# expansion_module_test_pads.net
KiCad netlist of a schematic drawn in EAGLE
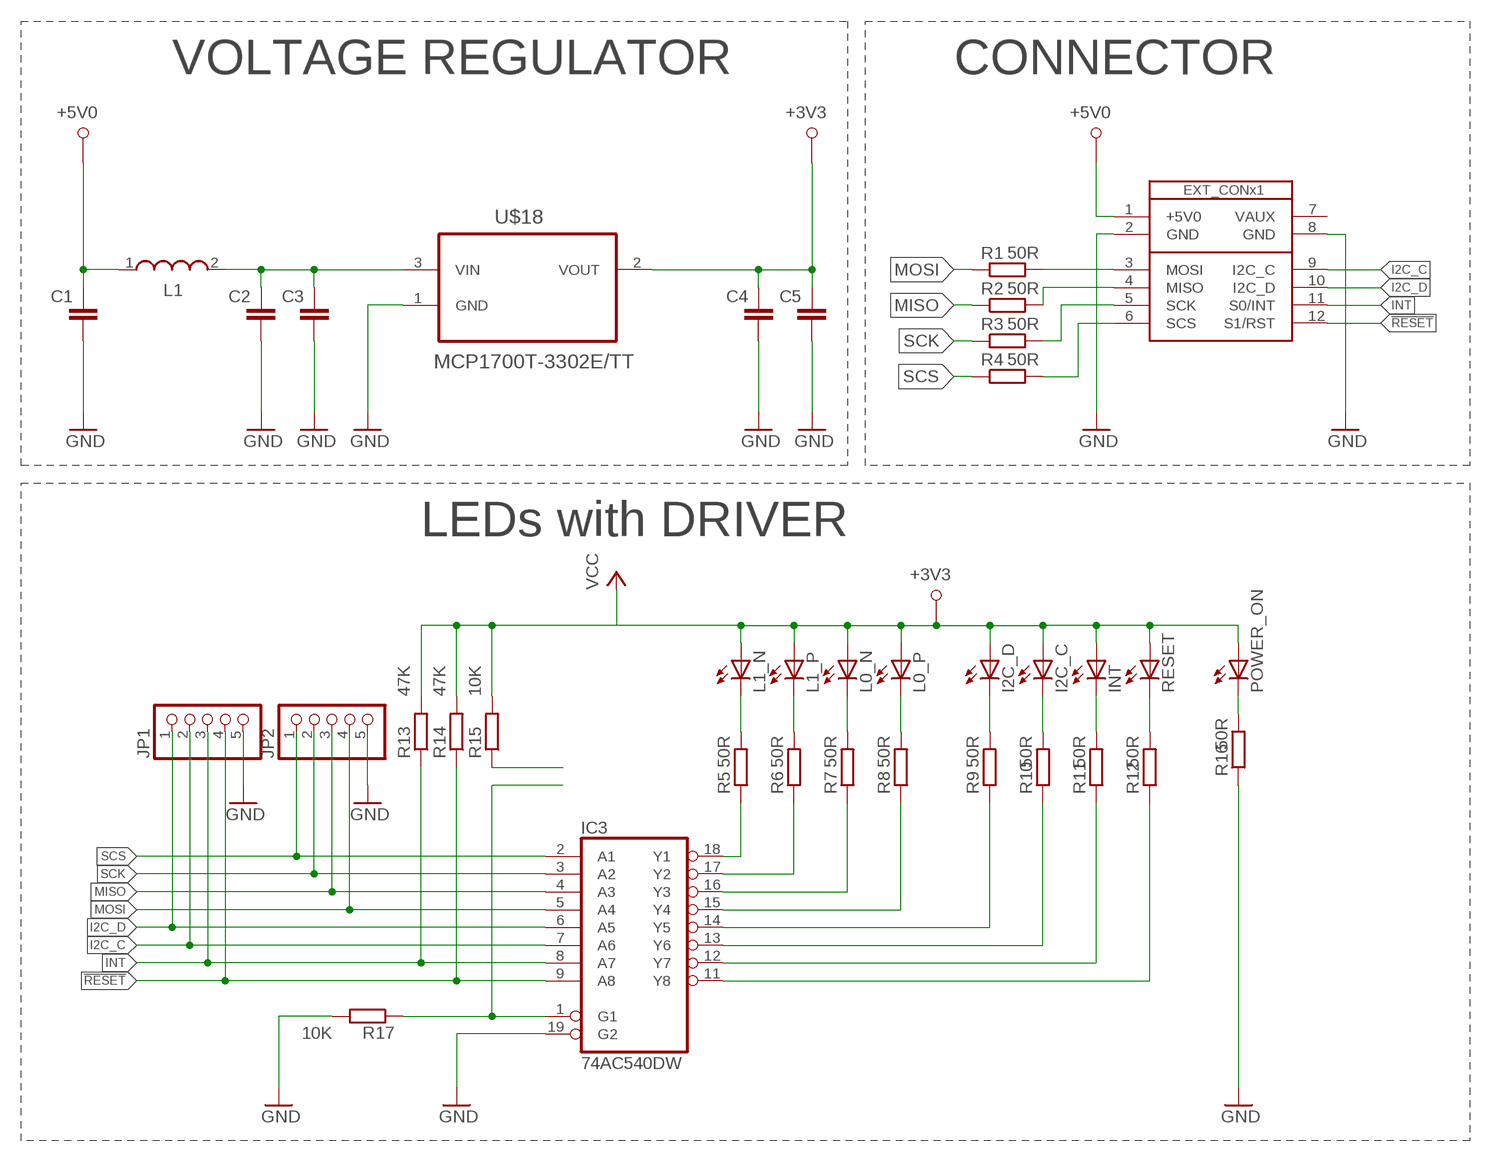
[diagram p0: schematic, sheet 1]

(export (version "E")
  (design (tool "Eeschema 10.0.6"))
  (components
    (comp (ref "C1")
      (value "C-EUC0805")
      (footprint "eagle-import:C0805")
      (libsource (lib "eagle-import") (part "C-EUC0805"))
    )
    (comp (ref "C2")
      (value "C-EUC0805")
      (footprint "eagle-import:C0805")
      (libsource (lib "eagle-import") (part "C-EUC0805"))
    )
    (comp (ref "C3")
      (value "C-EUC0805")
      (footprint "eagle-import:C0805")
      (libsource (lib "eagle-import") (part "C-EUC0805"))
    )
    (comp (ref "C4")
      (value "C-EUC0805")
      (footprint "eagle-import:C0805")
      (libsource (lib "eagle-import") (part "C-EUC0805"))
    )
    (comp (ref "C5")
      (value "C-EUC0805")
      (footprint "eagle-import:C0805")
      (libsource (lib "eagle-import") (part "C-EUC0805"))
    )
    (comp (ref "I2C_C")
      (value "LEDCHIPLED_0805")
      (footprint "eagle-import:CHIPLED_0805")
      (libsource (lib "eagle-import") (part "LEDCHIPLED_0805"))
    )
    (comp (ref "I2C_D")
      (value "LEDCHIPLED_0805")
      (footprint "eagle-import:CHIPLED_0805")
      (libsource (lib "eagle-import") (part "LEDCHIPLED_0805"))
    )
    (comp (ref "IC3")
      (value "74AC540DW")
      (footprint "eagle-import:SO20W")
      (libsource (lib "eagle-import") (part "74540DWAC"))
    )
    (comp (ref "INT")
      (value "LEDCHIPLED_0805")
      (footprint "eagle-import:CHIPLED_0805")
      (libsource (lib "eagle-import") (part "LEDCHIPLED_0805"))
    )
    (comp (ref "JP1")
      (value "PINHD-1X5")
      (footprint "eagle-import:1X05")
      (libsource (lib "eagle-import") (part "PINHD-1X5"))
    )
    (comp (ref "JP2")
      (value "PINHD-1X5")
      (footprint "eagle-import:1X05")
      (libsource (lib "eagle-import") (part "PINHD-1X5"))
    )
    (comp (ref "L0_N")
      (value "LEDCHIPLED_0805")
      (footprint "eagle-import:CHIPLED_0805")
      (libsource (lib "eagle-import") (part "LEDCHIPLED_0805"))
    )
    (comp (ref "L0_P")
      (value "LEDCHIPLED_0805")
      (footprint "eagle-import:CHIPLED_0805")
      (libsource (lib "eagle-import") (part "LEDCHIPLED_0805"))
    )
    (comp (ref "L1")
      (value "WE-LQ_1210")
      (footprint "eagle-import:WE-LQ_M")
      (libsource (lib "eagle-import") (part "WE-LQ_1210"))
    )
    (comp (ref "L1_N")
      (value "LEDCHIPLED_0805")
      (footprint "eagle-import:CHIPLED_0805")
      (libsource (lib "eagle-import") (part "LEDCHIPLED_0805"))
    )
    (comp (ref "L1_P")
      (value "LEDCHIPLED_0805")
      (footprint "eagle-import:CHIPLED_0805")
      (libsource (lib "eagle-import") (part "LEDCHIPLED_0805"))
    )
    (comp (ref "POWER_ON")
      (value "LEDCHIPLED_0805")
      (footprint "eagle-import:CHIPLED_0805")
      (libsource (lib "eagle-import") (part "LEDCHIPLED_0805"))
    )
    (comp (ref "R1")
      (value "50R")
      (footprint "eagle-import:R0805")
      (libsource (lib "eagle-import") (part "R-EU_R0805"))
    )
    (comp (ref "R2")
      (value "50R")
      (footprint "eagle-import:R0805")
      (libsource (lib "eagle-import") (part "R-EU_R0805"))
    )
    (comp (ref "R3")
      (value "50R")
      (footprint "eagle-import:R0805")
      (libsource (lib "eagle-import") (part "R-EU_R0805"))
    )
    (comp (ref "R4")
      (value "50R")
      (footprint "eagle-import:R0805")
      (libsource (lib "eagle-import") (part "R-EU_R0805"))
    )
    (comp (ref "R5")
      (value "50R")
      (footprint "eagle-import:R0805")
      (libsource (lib "eagle-import") (part "R-EU_R0805"))
    )
    (comp (ref "R6")
      (value "50R")
      (footprint "eagle-import:R0805")
      (libsource (lib "eagle-import") (part "R-EU_R0805"))
    )
    (comp (ref "R7")
      (value "50R")
      (footprint "eagle-import:R0805")
      (libsource (lib "eagle-import") (part "R-EU_R0805"))
    )
    (comp (ref "R8")
      (value "50R")
      (footprint "eagle-import:R0805")
      (libsource (lib "eagle-import") (part "R-EU_R0805"))
    )
    (comp (ref "R9")
      (value "50R")
      (footprint "eagle-import:R0805")
      (libsource (lib "eagle-import") (part "R-EU_R0805"))
    )
    (comp (ref "R10")
      (value "50R")
      (footprint "eagle-import:R0805")
      (libsource (lib "eagle-import") (part "R-EU_R0805"))
    )
    (comp (ref "R11")
      (value "50R")
      (footprint "eagle-import:R0805")
      (libsource (lib "eagle-import") (part "R-EU_R0805"))
    )
    (comp (ref "R12")
      (value "50R")
      (footprint "eagle-import:R0805")
      (libsource (lib "eagle-import") (part "R-EU_R0805"))
    )
    (comp (ref "R13")
      (value "47K")
      (footprint "eagle-import:R0805")
      (libsource (lib "eagle-import") (part "R-EU_R0805"))
    )
    (comp (ref "R14")
      (value "47K")
      (footprint "eagle-import:R0805")
      (libsource (lib "eagle-import") (part "R-EU_R0805"))
    )
    (comp (ref "R15")
      (value "10K")
      (footprint "eagle-import:R0805")
      (libsource (lib "eagle-import") (part "R-EU_R0805"))
    )
    (comp (ref "R16")
      (value "50R")
      (footprint "eagle-import:R0805")
      (libsource (lib "eagle-import") (part "R-EU_R0805"))
    )
    (comp (ref "R17")
      (value "10K")
      (footprint "eagle-import:R0805")
      (libsource (lib "eagle-import") (part "R-EU_R0805"))
    )
    (comp (ref "RESET")
      (value "LEDCHIPLED_0805")
      (footprint "eagle-import:CHIPLED_0805")
      (libsource (lib "eagle-import") (part "LEDCHIPLED_0805"))
    )
    (comp (ref "U$1")
      (value "SB_EXT_CON_X1_SPI")
      (footprint "eagle-import:SB_EXT_CON_X1_FULL")
      (libsource (lib "eagle-import") (part "SB_EXT_CON_X1_SPI"))
    )
    (comp (ref "U$18")
      (value "MCP1700T-3302E/TT")
      (footprint "eagle-import:SOT95P237X112-3N")
      (libsource (lib "eagle-import") (part "MCP1700T-3302E/TT"))
    )
  )
  (nets
    (net (code "1") (name "+3V3") (class "Default")
      (node (ref "C4") (pin "2") (pinfunction "2_2") (pintype "passive"))
      (node (ref "C5") (pin "2") (pinfunction "2_2") (pintype "passive"))
      (node (ref "I2C_C") (pin "A") (pinfunction "A_A") (pintype "passive"))
      (node (ref "I2C_D") (pin "A") (pinfunction "A_A") (pintype "passive"))
      (node (ref "INT") (pin "A") (pinfunction "A_A") (pintype "passive"))
      (node (ref "L0_N") (pin "A") (pinfunction "A_A") (pintype "passive"))
      (node (ref "L0_P") (pin "A") (pinfunction "A_A") (pintype "passive"))
      (node (ref "L1_N") (pin "A") (pinfunction "A_A") (pintype "passive"))
      (node (ref "L1_P") (pin "A") (pinfunction "A_A") (pintype "passive"))
      (node (ref "POWER_ON") (pin "A") (pinfunction "A_A") (pintype "passive"))
      (node (ref "R13") (pin "2") (pinfunction "2_2") (pintype "passive"))
      (node (ref "R14") (pin "2") (pinfunction "2_2") (pintype "passive"))
      (node (ref "R15") (pin "2") (pinfunction "2_2") (pintype "passive"))
      (node (ref "RESET") (pin "A") (pinfunction "A_A") (pintype "passive"))
      (node (ref "U$18") (pin "2") (pinfunction "VOUT_2") (pintype "output"))
    )
    (net (code "2") (name "+5V0") (class "Default")
      (node (ref "C1") (pin "2") (pinfunction "2_2") (pintype "passive"))
      (node (ref "L1") (pin "1") (pinfunction "1_1") (pintype "passive"))
      (node (ref "U$1") (pin "1") (pinfunction "+5V0_1") (pintype "bidirectional"))
    )
    (net (code "3") (name "/~{RESET}") (class "Default")
      (node (ref "IC3") (pin "9") (pinfunction "A8_9") (pintype "input"))
      (node (ref "JP1") (pin "4") (pinfunction "4_4") (pintype "passive"))
      (node (ref "R14") (pin "1") (pinfunction "1_1") (pintype "passive"))
      (node (ref "U$1") (pin "12") (pinfunction "S1/RST_12") (pintype "bidirectional"))
    )
    (net (code "4") (name "GND") (class "Default")
      (node (ref "C1") (pin "1") (pinfunction "1_1") (pintype "passive"))
      (node (ref "C2") (pin "1") (pinfunction "1_1") (pintype "passive"))
      (node (ref "C3") (pin "1") (pinfunction "1_1") (pintype "passive"))
      (node (ref "C4") (pin "1") (pinfunction "1_1") (pintype "passive"))
      (node (ref "C5") (pin "1") (pinfunction "1_1") (pintype "passive"))
      (node (ref "IC3") (pin "19") (pinfunction "G2_19") (pintype "input"))
      (node (ref "JP1") (pin "5") (pinfunction "5_5") (pintype "passive"))
      (node (ref "JP2") (pin "5") (pinfunction "5_5") (pintype "passive"))
      (node (ref "R16") (pin "1") (pinfunction "1_1") (pintype "passive"))
      (node (ref "R17") (pin "2") (pinfunction "2_2") (pintype "passive"))
      (node (ref "U$1") (pin "2") (pinfunction "GND_2") (pintype "bidirectional"))
      (node (ref "U$1") (pin "8") (pinfunction "GND_8") (pintype "bidirectional"))
      (node (ref "U$18") (pin "1") (pinfunction "GND_1") (pintype "passive"))
    )
    (net (code "5") (name "I2C_C") (class "Default")
      (node (ref "IC3") (pin "7") (pinfunction "A6_7") (pintype "input"))
      (node (ref "JP1") (pin "2") (pinfunction "2_2") (pintype "passive"))
      (node (ref "U$1") (pin "9") (pinfunction "I2C_C_9") (pintype "bidirectional"))
    )
    (net (code "6") (name "I2C_D") (class "Default")
      (node (ref "IC3") (pin "6") (pinfunction "A5_6") (pintype "input"))
      (node (ref "JP1") (pin "1") (pinfunction "1_1") (pintype "passive"))
      (node (ref "U$1") (pin "10") (pinfunction "I2C_D_10") (pintype "bidirectional"))
    )
    (net (code "7") (name "INT") (class "Default")
      (node (ref "IC3") (pin "8") (pinfunction "A7_8") (pintype "input"))
      (node (ref "JP1") (pin "3") (pinfunction "3_3") (pintype "passive"))
      (node (ref "R13") (pin "1") (pinfunction "1_1") (pintype "passive"))
      (node (ref "U$1") (pin "11") (pinfunction "S0/INT_11") (pintype "bidirectional"))
    )
    (net (code "8") (name "MISO") (class "Default")
      (node (ref "IC3") (pin "4") (pinfunction "A3_4") (pintype "input"))
      (node (ref "JP2") (pin "3") (pinfunction "3_3") (pintype "passive"))
      (node (ref "R2") (pin "1") (pinfunction "1_1") (pintype "passive"))
    )
    (net (code "9") (name "MOSI") (class "Default")
      (node (ref "IC3") (pin "5") (pinfunction "A4_5") (pintype "input"))
      (node (ref "JP2") (pin "4") (pinfunction "4_4") (pintype "passive"))
      (node (ref "R1") (pin "1") (pinfunction "1_1") (pintype "passive"))
    )
    (net (code "10") (name "Net-(I2C_C-PadC)") (class "Default")
      (node (ref "I2C_C") (pin "C") (pinfunction "C_C") (pintype "passive"))
      (node (ref "R10") (pin "2") (pinfunction "2_2") (pintype "passive"))
    )
    (net (code "11") (name "Net-(I2C_D-PadC)") (class "Default")
      (node (ref "I2C_D") (pin "C") (pinfunction "C_C") (pintype "passive"))
      (node (ref "R9") (pin "2") (pinfunction "2_2") (pintype "passive"))
    )
    (net (code "12") (name "Net-(IC3A-G1)") (class "Default")
      (node (ref "IC3") (pin "1") (pinfunction "G1_1") (pintype "input"))
      (node (ref "R17") (pin "1") (pinfunction "1_1") (pintype "passive"))
    )
    (net (code "13") (name "Net-(IC3A-Y1)") (class "Default")
      (node (ref "IC3") (pin "18") (pinfunction "Y1_18") (pintype "tri_state"))
      (node (ref "R5") (pin "1") (pinfunction "1_1") (pintype "passive"))
    )
    (net (code "14") (name "Net-(IC3A-Y2)") (class "Default")
      (node (ref "IC3") (pin "17") (pinfunction "Y2_17") (pintype "tri_state"))
      (node (ref "R6") (pin "1") (pinfunction "1_1") (pintype "passive"))
    )
    (net (code "15") (name "Net-(IC3A-Y3)") (class "Default")
      (node (ref "IC3") (pin "16") (pinfunction "Y3_16") (pintype "tri_state"))
      (node (ref "R7") (pin "1") (pinfunction "1_1") (pintype "passive"))
    )
    (net (code "16") (name "Net-(IC3A-Y4)") (class "Default")
      (node (ref "IC3") (pin "15") (pinfunction "Y4_15") (pintype "tri_state"))
      (node (ref "R8") (pin "1") (pinfunction "1_1") (pintype "passive"))
    )
    (net (code "17") (name "Net-(IC3A-Y5)") (class "Default")
      (node (ref "IC3") (pin "14") (pinfunction "Y5_14") (pintype "tri_state"))
      (node (ref "R9") (pin "1") (pinfunction "1_1") (pintype "passive"))
    )
    (net (code "18") (name "Net-(IC3A-Y6)") (class "Default")
      (node (ref "IC3") (pin "13") (pinfunction "Y6_13") (pintype "tri_state"))
      (node (ref "R10") (pin "1") (pinfunction "1_1") (pintype "passive"))
    )
    (net (code "19") (name "Net-(IC3A-Y7)") (class "Default")
      (node (ref "IC3") (pin "12") (pinfunction "Y7_12") (pintype "tri_state"))
      (node (ref "R11") (pin "1") (pinfunction "1_1") (pintype "passive"))
    )
    (net (code "20") (name "Net-(IC3A-Y8)") (class "Default")
      (node (ref "IC3") (pin "11") (pinfunction "Y8_11") (pintype "tri_state"))
      (node (ref "R12") (pin "1") (pinfunction "1_1") (pintype "passive"))
    )
    (net (code "21") (name "Net-(INT-PadC)") (class "Default")
      (node (ref "INT") (pin "C") (pinfunction "C_C") (pintype "passive"))
      (node (ref "R11") (pin "2") (pinfunction "2_2") (pintype "passive"))
    )
    (net (code "22") (name "Net-(L0_N-PadC)") (class "Default")
      (node (ref "L0_N") (pin "C") (pinfunction "C_C") (pintype "passive"))
      (node (ref "R7") (pin "2") (pinfunction "2_2") (pintype "passive"))
    )
    (net (code "23") (name "Net-(L0_P-PadC)") (class "Default")
      (node (ref "L0_P") (pin "C") (pinfunction "C_C") (pintype "passive"))
      (node (ref "R8") (pin "2") (pinfunction "2_2") (pintype "passive"))
    )
    (net (code "24") (name "Net-(L1_N-PadC)") (class "Default")
      (node (ref "L1_N") (pin "C") (pinfunction "C_C") (pintype "passive"))
      (node (ref "R5") (pin "2") (pinfunction "2_2") (pintype "passive"))
    )
    (net (code "25") (name "Net-(L1_P-PadC)") (class "Default")
      (node (ref "L1_P") (pin "C") (pinfunction "C_C") (pintype "passive"))
      (node (ref "R6") (pin "2") (pinfunction "2_2") (pintype "passive"))
    )
    (net (code "26") (name "Net-(POWER_ON-PadC)") (class "Default")
      (node (ref "POWER_ON") (pin "C") (pinfunction "C_C") (pintype "passive"))
      (node (ref "R16") (pin "2") (pinfunction "2_2") (pintype "passive"))
    )
    (net (code "27") (name "Net-(R12-Pad2)") (class "Default")
      (node (ref "R12") (pin "2") (pinfunction "2_2") (pintype "passive"))
      (node (ref "RESET") (pin "C") (pinfunction "C_C") (pintype "passive"))
    )
    (net (code "28") (name "Net-(U$1-MISO)") (class "Default")
      (node (ref "R2") (pin "2") (pinfunction "2_2") (pintype "passive"))
      (node (ref "U$1") (pin "4") (pinfunction "MISO_4") (pintype "bidirectional"))
    )
    (net (code "29") (name "Net-(U$1-MOSI)") (class "Default")
      (node (ref "R1") (pin "2") (pinfunction "2_2") (pintype "passive"))
      (node (ref "U$1") (pin "3") (pinfunction "MOSI_3") (pintype "bidirectional"))
    )
    (net (code "30") (name "Net-(U$1-SCK)") (class "Default")
      (node (ref "R3") (pin "2") (pinfunction "2_2") (pintype "passive"))
      (node (ref "U$1") (pin "5") (pinfunction "SCK_5") (pintype "bidirectional"))
    )
    (net (code "31") (name "Net-(U$1-SCS)") (class "Default")
      (node (ref "R4") (pin "2") (pinfunction "2_2") (pintype "passive"))
      (node (ref "U$1") (pin "6") (pinfunction "SCS_6") (pintype "bidirectional"))
    )
    (net (code "32") (name "Net-(U$18-VIN)") (class "Default")
      (node (ref "C2") (pin "2") (pinfunction "2_2") (pintype "passive"))
      (node (ref "C3") (pin "2") (pinfunction "2_2") (pintype "passive"))
      (node (ref "L1") (pin "2") (pinfunction "2_2") (pintype "passive"))
      (node (ref "U$18") (pin "3") (pinfunction "VIN_3") (pintype "input"))
    )
    (net (code "33") (name "SCK") (class "Default")
      (node (ref "IC3") (pin "3") (pinfunction "A2_3") (pintype "input"))
      (node (ref "JP2") (pin "2") (pinfunction "2_2") (pintype "passive"))
      (node (ref "R3") (pin "1") (pinfunction "1_1") (pintype "passive"))
    )
    (net (code "34") (name "SCS") (class "Default")
      (node (ref "IC3") (pin "2") (pinfunction "A1_2") (pintype "input"))
      (node (ref "JP2") (pin "1") (pinfunction "1_1") (pintype "passive"))
      (node (ref "R4") (pin "1") (pinfunction "1_1") (pintype "passive"))
    )
    (net (code "36") (name "unconnected-(R15-Pad1)") (class "Default")
      (node (ref "R15") (pin "1") (pinfunction "1_1") (pintype "passive"))
    )
    (net (code "37") (name "unconnected-(U$1-VAUX-Pad7)") (class "Default")
      (node (ref "U$1") (pin "7") (pinfunction "VAUX_7") (pintype "bidirectional"))
    )
  )
)
